# Sheet1.net
KiCad netlist of a schematic drawn in Altium Designer
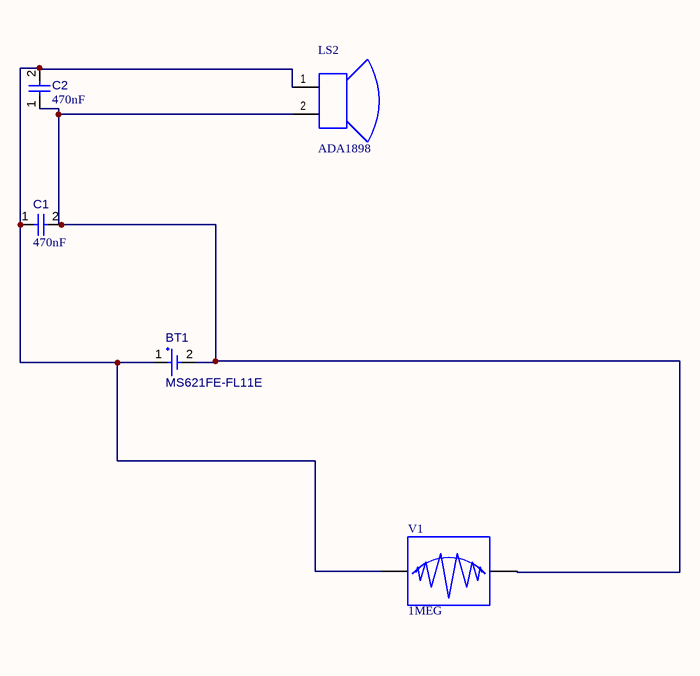
[diagram p0: Sheet1.SchDoc]

(export (version "E")
  (design (tool "Eeschema 10.0.6"))
  (components
    (comp (ref "BT1")
      (value "MS621FE-FL11E")
      (footprint "SEIK-MS621FE-FL11E-2_V")
      (description "MS Lihium Rechargeable Battery, 3 V, -20 to 60 degC, Tray")
      (libsource (lib "16072020") (part "CMP-00622-2"))
    )
    (comp (ref "C1")
      (value "470nF")
      (footprint "CAPC0402(1005)60_L")
      (description "Chip Capacitor, 470nF +/-40%, 10V, 0402, Thickness 0.6 mm")
      (fields (field (name "TOLERANCE") "20%") (field (name "Comment") "Capacitor 470nF +/-40% 10V 0402"))
      (libsource (lib "16072020") (part "CAP-NP-2"))
    )
    (comp (ref "C2")
      (value "470nF")
      (footprint "CAPC0402(1005)60_L")
      (description "Chip Capacitor, 470nF +/-40%, 10V, 0402, Thickness 0.6 mm")
      (fields (field (name "TOLERANCE") "20%") (field (name "Comment") "Capacitor 470nF +/-40% 10V 0402"))
      (libsource (lib "16072020") (part "CAP-NP-2"))
    )
    (comp (ref "LS2")
      (value "ADA1898")
      (footprint "ADAI-ADA1898")
      (description "Mini Speaker, 8 Ohm, 0.2 Wmax, -10 to 40 degC, 2-Pin THD, RoHS")
      (fields (field (name "MANUFACTURER") "Adafruit Industries"))
      (libsource (lib "16072020") (part "SPEAKER-2"))
    )
    (comp (ref "V1")
      (value "Amplitude Modulator Voltage Source")
      (fields (field (name "FC") "1MEG"))
      (libsource (lib "Simulation Generic Components") (part "AM"))
    )
  )
  (nets
    (net (code "1") (name "Net-(BT1-+)") (class "Default")
      (node (ref "BT1") (pin "1") (pinfunction "+_1") (pintype "passive"))
      (node (ref "C1") (pin "1") (pinfunction "1_1") (pintype "passive"))
      (node (ref "C2") (pin "2") (pinfunction "2_2") (pintype "passive"))
      (node (ref "LS2") (pin "1") (pinfunction "+_1") (pintype "passive"))
      (node (ref "V1") (pin "1") (pinfunction "IN_1") (pintype "passive"))
    )
    (net (code "2") (name "Net-(BT1--)") (class "Default")
      (node (ref "BT1") (pin "2") (pinfunction "-_2") (pintype "passive"))
      (node (ref "C1") (pin "2") (pinfunction "2_2") (pintype "passive"))
      (node (ref "C2") (pin "1") (pinfunction "1_1") (pintype "passive"))
      (node (ref "LS2") (pin "2") (pinfunction "-_2") (pintype "passive"))
      (node (ref "V1") (pin "2") (pinfunction "OUT_2") (pintype "passive"))
    )
  )
)
